# RaspiOMix.net
KiCad netlist of a schematic drawn in EAGLE
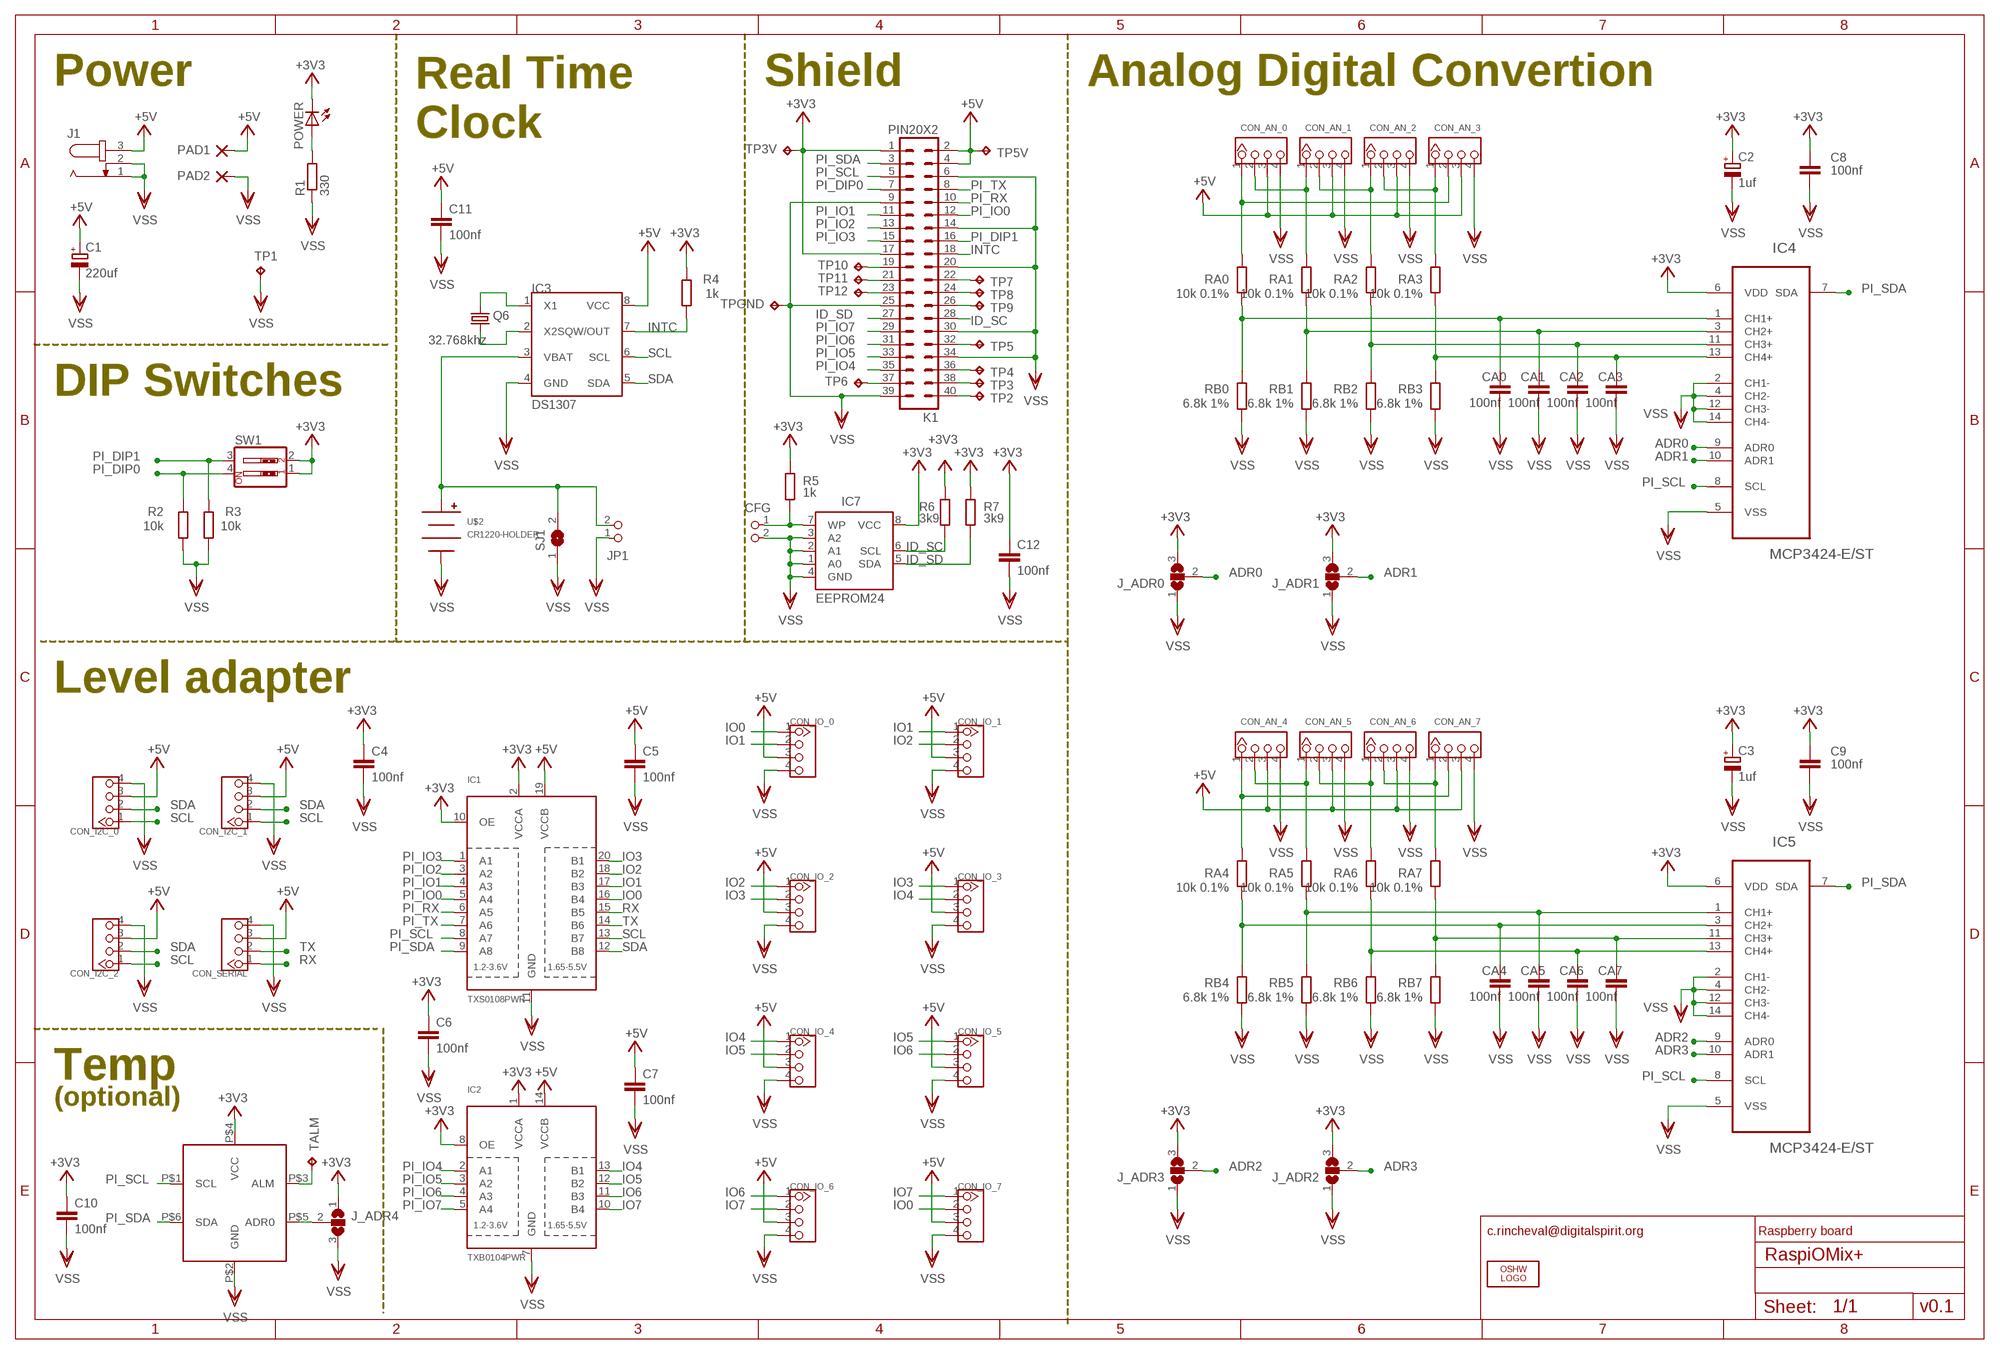
[diagram p0: schematic, sheet 1]

(export (version "E")
  (design (tool "Eeschema 10.0.6"))
  (components
    (comp (ref "C1")
      (value "220uf")
      (footprint "eagle-import:PANASONIC_D")
      (libsource (lib "eagle-import") (part "CPOL-EUD"))
    )
    (comp (ref "C2")
      (value "1uf")
      (footprint "eagle-import:B_3528-21R")
      (libsource (lib "eagle-import") (part "CPOL-EUB/3528-21R"))
    )
    (comp (ref "C3")
      (value "1uf")
      (footprint "eagle-import:B_3528-21R")
      (libsource (lib "eagle-import") (part "CPOL-EUB/3528-21R"))
    )
    (comp (ref "C4")
      (value "100nf")
      (footprint "eagle-import:C0805")
      (libsource (lib "eagle-import") (part "C-EUC0805"))
    )
    (comp (ref "C5")
      (value "100nf")
      (footprint "eagle-import:C0805")
      (libsource (lib "eagle-import") (part "C-EUC0805"))
    )
    (comp (ref "C6")
      (value "100nf")
      (footprint "eagle-import:C0805")
      (libsource (lib "eagle-import") (part "C-EUC0805"))
    )
    (comp (ref "C7")
      (value "100nf")
      (footprint "eagle-import:C0805")
      (libsource (lib "eagle-import") (part "C-EUC0805"))
    )
    (comp (ref "C8")
      (value "100nf")
      (footprint "eagle-import:C0805")
      (libsource (lib "eagle-import") (part "C-EUC0805"))
    )
    (comp (ref "C9")
      (value "100nf")
      (footprint "eagle-import:C0805")
      (libsource (lib "eagle-import") (part "C-EUC0805"))
    )
    (comp (ref "C10")
      (value "100nf")
      (footprint "eagle-import:C0805")
      (libsource (lib "eagle-import") (part "C-EUC0805"))
    )
    (comp (ref "C11")
      (value "100nf")
      (footprint "eagle-import:C0805")
      (libsource (lib "eagle-import") (part "C-EUC0805"))
    )
    (comp (ref "C12")
      (value "100nf")
      (footprint "eagle-import:C0805K")
      (libsource (lib "eagle-import") (part "resistor_C-EUC0805K"))
    )
    (comp (ref "CA0")
      (value "100nf")
      (footprint "eagle-import:C0805")
      (libsource (lib "eagle-import") (part "C-EUC0805"))
    )
    (comp (ref "CA1")
      (value "100nf")
      (footprint "eagle-import:C0805")
      (libsource (lib "eagle-import") (part "C-EUC0805"))
    )
    (comp (ref "CA2")
      (value "100nf")
      (footprint "eagle-import:C0805")
      (libsource (lib "eagle-import") (part "C-EUC0805"))
    )
    (comp (ref "CA3")
      (value "100nf")
      (footprint "eagle-import:C0805")
      (libsource (lib "eagle-import") (part "C-EUC0805"))
    )
    (comp (ref "CA4")
      (value "100nf")
      (footprint "eagle-import:C0805")
      (libsource (lib "eagle-import") (part "C-EUC0805"))
    )
    (comp (ref "CA5")
      (value "100nf")
      (footprint "eagle-import:C0805")
      (libsource (lib "eagle-import") (part "C-EUC0805"))
    )
    (comp (ref "CA6")
      (value "100nf")
      (footprint "eagle-import:C0805")
      (libsource (lib "eagle-import") (part "C-EUC0805"))
    )
    (comp (ref "CA7")
      (value "100nf")
      (footprint "eagle-import:C0805")
      (libsource (lib "eagle-import") (part "C-EUC0805"))
    )
    (comp (ref "CFG")
      (value "PIN2_100")
      (footprint "eagle-import:PIN_W_2")
      (libsource (lib "eagle-import") (part "PIN2_100"))
    )
    (comp (ref "CON_AN_0")
      (value "TWIG-4P-2.0-2.0")
      (footprint "eagle-import:4P-2.0")
      (libsource (lib "eagle-import") (part "TWIG-4P-2.0-2.0"))
    )
    (comp (ref "CON_AN_1")
      (value "TWIG-4P-2.0-2.0")
      (footprint "eagle-import:4P-2.0")
      (libsource (lib "eagle-import") (part "TWIG-4P-2.0-2.0"))
    )
    (comp (ref "CON_AN_2")
      (value "TWIG-4P-2.0-2.0")
      (footprint "eagle-import:4P-2.0")
      (libsource (lib "eagle-import") (part "TWIG-4P-2.0-2.0"))
    )
    (comp (ref "CON_AN_3")
      (value "TWIG-4P-2.0-2.0")
      (footprint "eagle-import:4P-2.0")
      (libsource (lib "eagle-import") (part "TWIG-4P-2.0-2.0"))
    )
    (comp (ref "CON_AN_4")
      (value "TWIG-4P-2.0-2.0")
      (footprint "eagle-import:4P-2.0")
      (libsource (lib "eagle-import") (part "TWIG-4P-2.0-2.0"))
    )
    (comp (ref "CON_AN_5")
      (value "TWIG-4P-2.0-2.0")
      (footprint "eagle-import:4P-2.0")
      (libsource (lib "eagle-import") (part "TWIG-4P-2.0-2.0"))
    )
    (comp (ref "CON_AN_6")
      (value "TWIG-4P-2.0-2.0")
      (footprint "eagle-import:4P-2.0")
      (libsource (lib "eagle-import") (part "TWIG-4P-2.0-2.0"))
    )
    (comp (ref "CON_AN_7")
      (value "TWIG-4P-2.0-2.0")
      (footprint "eagle-import:4P-2.0")
      (libsource (lib "eagle-import") (part "TWIG-4P-2.0-2.0"))
    )
    (comp (ref "CON_I2C_0")
      (value "TWIG-4P-2.0-2.0")
      (footprint "eagle-import:4P-2.0")
      (libsource (lib "eagle-import") (part "TWIG-4P-2.0-2.0"))
    )
    (comp (ref "CON_I2C_1")
      (value "TWIG-4P-2.0-2.0")
      (footprint "eagle-import:4P-2.0")
      (libsource (lib "eagle-import") (part "TWIG-4P-2.0-2.0"))
    )
    (comp (ref "CON_I2C_2")
      (value "TWIG-4P-2.0-2.0")
      (footprint "eagle-import:4P-2.0")
      (libsource (lib "eagle-import") (part "TWIG-4P-2.0-2.0"))
    )
    (comp (ref "CON_IO_0")
      (value "TWIG-4P-2.0-2.0")
      (footprint "eagle-import:4P-2.0")
      (libsource (lib "eagle-import") (part "TWIG-4P-2.0-2.0"))
    )
    (comp (ref "CON_IO_1")
      (value "TWIG-4P-2.0-2.0")
      (footprint "eagle-import:4P-2.0")
      (libsource (lib "eagle-import") (part "TWIG-4P-2.0-2.0"))
    )
    (comp (ref "CON_IO_2")
      (value "TWIG-4P-2.0-2.0")
      (footprint "eagle-import:4P-2.0")
      (libsource (lib "eagle-import") (part "TWIG-4P-2.0-2.0"))
    )
    (comp (ref "CON_IO_3")
      (value "TWIG-4P-2.0-2.0")
      (footprint "eagle-import:4P-2.0")
      (libsource (lib "eagle-import") (part "TWIG-4P-2.0-2.0"))
    )
    (comp (ref "CON_IO_4")
      (value "TWIG-4P-2.0-2.0")
      (footprint "eagle-import:4P-2.0")
      (libsource (lib "eagle-import") (part "TWIG-4P-2.0-2.0"))
    )
    (comp (ref "CON_IO_5")
      (value "TWIG-4P-2.0-2.0")
      (footprint "eagle-import:4P-2.0")
      (libsource (lib "eagle-import") (part "TWIG-4P-2.0-2.0"))
    )
    (comp (ref "CON_IO_6")
      (value "TWIG-4P-2.0-2.0")
      (footprint "eagle-import:4P-2.0")
      (libsource (lib "eagle-import") (part "TWIG-4P-2.0-2.0"))
    )
    (comp (ref "CON_IO_7")
      (value "TWIG-4P-2.0-2.0")
      (footprint "eagle-import:4P-2.0")
      (libsource (lib "eagle-import") (part "TWIG-4P-2.0-2.0"))
    )
    (comp (ref "CON_SERIAL")
      (value "TWIG-4P-2.0-2.0")
      (footprint "eagle-import:4P-2.0")
      (libsource (lib "eagle-import") (part "TWIG-4P-2.0-2.0"))
    )
    (comp (ref "IC1")
      (value "TXS0108PWR")
      (footprint "eagle-import:TSSOP20")
      (libsource (lib "eagle-import") (part "TXB0108PWR"))
    )
    (comp (ref "IC2")
      (value "TXB0104PWR")
      (footprint "eagle-import:TSSOP14")
      (libsource (lib "eagle-import") (part "TXB0104PWR"))
    )
    (comp (ref "IC3")
      (value "DS1307")
      (footprint "eagle-import:SOIC-8")
      (libsource (lib "eagle-import") (part "DS1307"))
    )
    (comp (ref "IC4")
      (value "MCP3424-E/ST")
      (footprint "eagle-import:SOP65P640X120-14N")
      (libsource (lib "eagle-import") (part "MCP3424-E/ST"))
    )
    (comp (ref "IC5")
      (value "MCP3424-E/ST")
      (footprint "eagle-import:SOP65P640X120-14N")
      (libsource (lib "eagle-import") (part "MCP3424-E/ST"))
    )
    (comp (ref "IC6")
      (value "TMP101")
      (footprint "eagle-import:SOT23-6")
      (libsource (lib "eagle-import") (part "TMP101"))
    )
    (comp (ref "IC7")
      (value "EEPROM24")
      (footprint "eagle-import:SOIC8")
      (libsource (lib "eagle-import") (part "EEPROM24"))
    )
    (comp (ref "J1")
      (value "JACK-PLUG0")
      (footprint "eagle-import:SPC4077")
      (libsource (lib "eagle-import") (part "JACK-PLUG0"))
    )
    (comp (ref "JP1")
      (value "PIN2_100")
      (footprint "eagle-import:PIN_W_2")
      (libsource (lib "eagle-import") (part "PIN2_100"))
    )
    (comp (ref "J_ADR0")
      (value "SJ2W")
      (footprint "eagle-import:SJ_2")
      (libsource (lib "eagle-import") (part "SJ2W"))
    )
    (comp (ref "J_ADR1")
      (value "SJ2W")
      (footprint "eagle-import:SJ_2")
      (libsource (lib "eagle-import") (part "SJ2W"))
    )
    (comp (ref "J_ADR2")
      (value "SJ2W")
      (footprint "eagle-import:SJ_2")
      (libsource (lib "eagle-import") (part "SJ2W"))
    )
    (comp (ref "J_ADR3")
      (value "SJ2W")
      (footprint "eagle-import:SJ_2")
      (libsource (lib "eagle-import") (part "SJ2W"))
    )
    (comp (ref "J_ADR4")
      (value "SJ2W")
      (footprint "eagle-import:SJ_2")
      (libsource (lib "eagle-import") (part "SJ2W"))
    )
    (comp (ref "K1")
      (value "PIN20X2")
      (footprint "eagle-import:PIN_20X2")
      (libsource (lib "eagle-import") (part "PIN20X2"))
    )
    (comp (ref "LOGO1")
      (value "OSHW_LOGO_FILLX0350-NT")
      (footprint "eagle-import:OSHW_FILLX350_NOTEXT")
      (libsource (lib "eagle-import") (part "OSHW_LOGO_FILLX0350-NT"))
    )
    (comp (ref "PAD1")
      (value "WIREPAD3,17/1,3")
      (footprint "eagle-import:3,17_1,3")
      (libsource (lib "eagle-import") (part "WIREPAD3,17/1,3"))
    )
    (comp (ref "PAD2")
      (value "WIREPAD3,17/1,3")
      (footprint "eagle-import:3,17_1,3")
      (libsource (lib "eagle-import") (part "WIREPAD3,17/1,3"))
    )
    (comp (ref "POWER")
      (value "LEDCHIPLED_0805")
      (footprint "eagle-import:CHIPLED_0805")
      (libsource (lib "eagle-import") (part "LEDCHIPLED_0805"))
    )
    (comp (ref "Q6")
      (value "32.768khz")
      (footprint "eagle-import:TC26H")
      (libsource (lib "eagle-import") (part "CRYSTALTC26H"))
    )
    (comp (ref "R1")
      (value "330")
      (footprint "eagle-import:M0805")
      (libsource (lib "eagle-import") (part "R-EU_M0805"))
    )
    (comp (ref "R2")
      (value "10k")
      (footprint "eagle-import:M0805")
      (libsource (lib "eagle-import") (part "R-EU_M0805"))
    )
    (comp (ref "R3")
      (value "10k")
      (footprint "eagle-import:M0805")
      (libsource (lib "eagle-import") (part "R-EU_M0805"))
    )
    (comp (ref "R4")
      (value "1k")
      (footprint "eagle-import:M0805")
      (libsource (lib "eagle-import") (part "R-EU_M0805"))
    )
    (comp (ref "R5")
      (value "1k")
      (footprint "eagle-import:M0805")
      (fields (field (name "TOLERANCE") "5%"))
      (libsource (lib "eagle-import") (part "resistor_R-EU_M0805"))
    )
    (comp (ref "R6")
      (value "3k9")
      (footprint "eagle-import:M0805")
      (fields (field (name "TOLERANCE") "5%"))
      (libsource (lib "eagle-import") (part "resistor_R-EU_M0805"))
    )
    (comp (ref "R7")
      (value "3k9")
      (footprint "eagle-import:M0805")
      (fields (field (name "TOLERANCE") "5%"))
      (libsource (lib "eagle-import") (part "resistor_R-EU_M0805"))
    )
    (comp (ref "RA0")
      (value "10k 0.1%")
      (footprint "eagle-import:M0805")
      (libsource (lib "eagle-import") (part "R-EU_M0805"))
    )
    (comp (ref "RA1")
      (value "10k 0.1%")
      (footprint "eagle-import:M0805")
      (libsource (lib "eagle-import") (part "R-EU_M0805"))
    )
    (comp (ref "RA2")
      (value "10k 0.1%")
      (footprint "eagle-import:M0805")
      (libsource (lib "eagle-import") (part "R-EU_M0805"))
    )
    (comp (ref "RA3")
      (value "10k 0.1%")
      (footprint "eagle-import:M0805")
      (libsource (lib "eagle-import") (part "R-EU_M0805"))
    )
    (comp (ref "RA4")
      (value "10k 0.1%")
      (footprint "eagle-import:M0805")
      (libsource (lib "eagle-import") (part "R-EU_M0805"))
    )
    (comp (ref "RA5")
      (value "10k 0.1%")
      (footprint "eagle-import:M0805")
      (libsource (lib "eagle-import") (part "R-EU_M0805"))
    )
    (comp (ref "RA6")
      (value "10k 0.1%")
      (footprint "eagle-import:M0805")
      (libsource (lib "eagle-import") (part "R-EU_M0805"))
    )
    (comp (ref "RA7")
      (value "10k 0.1%")
      (footprint "eagle-import:M0805")
      (libsource (lib "eagle-import") (part "R-EU_M0805"))
    )
    (comp (ref "RB0")
      (value "6.8k 1%")
      (footprint "eagle-import:M0805")
      (libsource (lib "eagle-import") (part "R-EU_M0805"))
    )
    (comp (ref "RB1")
      (value "6.8k 1%")
      (footprint "eagle-import:M0805")
      (libsource (lib "eagle-import") (part "R-EU_M0805"))
    )
    (comp (ref "RB2")
      (value "6.8k 1%")
      (footprint "eagle-import:M0805")
      (libsource (lib "eagle-import") (part "R-EU_M0805"))
    )
    (comp (ref "RB3")
      (value "6.8k 1%")
      (footprint "eagle-import:M0805")
      (libsource (lib "eagle-import") (part "R-EU_M0805"))
    )
    (comp (ref "RB4")
      (value "6.8k 1%")
      (footprint "eagle-import:M0805")
      (libsource (lib "eagle-import") (part "R-EU_M0805"))
    )
    (comp (ref "RB5")
      (value "6.8k 1%")
      (footprint "eagle-import:M0805")
      (libsource (lib "eagle-import") (part "R-EU_M0805"))
    )
    (comp (ref "RB6")
      (value "6.8k 1%")
      (footprint "eagle-import:M0805")
      (libsource (lib "eagle-import") (part "R-EU_M0805"))
    )
    (comp (ref "RB7")
      (value "6.8k 1%")
      (footprint "eagle-import:M0805")
      (libsource (lib "eagle-import") (part "R-EU_M0805"))
    )
    (comp (ref "SJ1") (value "SJ") (footprint "eagle-import:SJ") (libsource (lib "eagle-import") (part "SJ")))
    (comp (ref "SW1")
      (value "SW_DIP-2")
      (footprint "eagle-import:EDG-02")
      (libsource (lib "eagle-import") (part "SW_DIP-2"))
    )
    (comp (ref "TALM")
      (value "TPTP12R")
      (footprint "eagle-import:TP12R")
      (libsource (lib "eagle-import") (part "TPTP12R"))
    )
    (comp (ref "TP1")
      (value "TPPAD1-13")
      (footprint "eagle-import:P1-13")
      (libsource (lib "eagle-import") (part "TPPAD1-13"))
    )
    (comp (ref "TP2")
      (value "TPTP12R")
      (footprint "eagle-import:TP12R")
      (libsource (lib "eagle-import") (part "TPTP12R"))
    )
    (comp (ref "TP3")
      (value "TPTP12R")
      (footprint "eagle-import:TP12R")
      (libsource (lib "eagle-import") (part "TPTP12R"))
    )
    (comp (ref "TP3V")
      (value "TPTP12R")
      (footprint "eagle-import:TP12R")
      (libsource (lib "eagle-import") (part "TPTP12R"))
    )
    (comp (ref "TP4")
      (value "TPTP12R")
      (footprint "eagle-import:TP12R")
      (libsource (lib "eagle-import") (part "TPTP12R"))
    )
    (comp (ref "TP5")
      (value "TPTP12R")
      (footprint "eagle-import:TP12R")
      (libsource (lib "eagle-import") (part "TPTP12R"))
    )
    (comp (ref "TP5V")
      (value "TPTP12R")
      (footprint "eagle-import:TP12R")
      (libsource (lib "eagle-import") (part "TPTP12R"))
    )
    (comp (ref "TP6")
      (value "TPTP12R")
      (footprint "eagle-import:TP12R")
      (libsource (lib "eagle-import") (part "TPTP12R"))
    )
    (comp (ref "TP7")
      (value "TPTP12R")
      (footprint "eagle-import:TP12R")
      (libsource (lib "eagle-import") (part "TPTP12R"))
    )
    (comp (ref "TP8")
      (value "TPTP12R")
      (footprint "eagle-import:TP12R")
      (libsource (lib "eagle-import") (part "TPTP12R"))
    )
    (comp (ref "TP9")
      (value "TPTP12R")
      (footprint "eagle-import:TP12R")
      (libsource (lib "eagle-import") (part "TPTP12R"))
    )
    (comp (ref "TP10")
      (value "TPTP12R")
      (footprint "eagle-import:TP12R")
      (libsource (lib "eagle-import") (part "TPTP12R"))
    )
    (comp (ref "TP11")
      (value "TPTP12R")
      (footprint "eagle-import:TP12R")
      (libsource (lib "eagle-import") (part "TPTP12R"))
    )
    (comp (ref "TP12")
      (value "TPTP12R")
      (footprint "eagle-import:TP12R")
      (libsource (lib "eagle-import") (part "TPTP12R"))
    )
    (comp (ref "TPGND")
      (value "TPTP12R")
      (footprint "eagle-import:TP12R")
      (libsource (lib "eagle-import") (part "TPTP12R"))
    )
    (comp (ref "U$2")
      (value "CR1220-HOLDER")
      (footprint "eagle-import:HARWIN-CR1220")
      (libsource (lib "eagle-import") (part "CR1220-HOLDER"))
    )
  )
  (nets
    (net (code "1") (name "+3V3") (class "Default")
      (node (ref "C10") (pin "1") (pinfunction "1_1") (pintype "passive"))
      (node (ref "C12") (pin "1") (pinfunction "1_1") (pintype "passive"))
      (node (ref "C2") (pin "+") (pinfunction "+_+") (pintype "passive"))
      (node (ref "C3") (pin "+") (pinfunction "+_+") (pintype "passive"))
      (node (ref "C4") (pin "1") (pinfunction "1_1") (pintype "passive"))
      (node (ref "C6") (pin "1") (pinfunction "1_1") (pintype "passive"))
      (node (ref "C8") (pin "2") (pinfunction "2_2") (pintype "passive"))
      (node (ref "C9") (pin "2") (pinfunction "2_2") (pintype "passive"))
      (node (ref "IC1") (pin "10") (pinfunction "OE_10") (pintype "bidirectional"))
      (node (ref "IC1") (pin "2") (pinfunction "VCCA_2") (pintype "bidirectional"))
      (node (ref "IC2") (pin "1") (pinfunction "VCCA_1") (pintype "bidirectional"))
      (node (ref "IC2") (pin "8") (pinfunction "OE_8") (pintype "bidirectional"))
      (node (ref "IC4") (pin "6") (pinfunction "VDD_6") (pintype "power_in"))
      (node (ref "IC5") (pin "6") (pinfunction "VDD_6") (pintype "power_in"))
      (node (ref "IC6") (pin "P$4") (pinfunction "VCC_P$4") (pintype "power_in"))
      (node (ref "IC7") (pin "8") (pinfunction "VCC_8") (pintype "power_in"))
      (node (ref "J_ADR0") (pin "3") (pinfunction "3_3") (pintype "passive"))
      (node (ref "J_ADR1") (pin "3") (pinfunction "3_3") (pintype "passive"))
      (node (ref "J_ADR2") (pin "3") (pinfunction "3_3") (pintype "passive"))
      (node (ref "J_ADR3") (pin "3") (pinfunction "3_3") (pintype "passive"))
      (node (ref "J_ADR4") (pin "1") (pinfunction "1_1") (pintype "passive"))
      (node (ref "K1") (pin "1") (pinfunction "1_1") (pintype "passive"))
      (node (ref "K1") (pin "17") (pinfunction "17_17") (pintype "passive"))
      (node (ref "POWER") (pin "C") (pinfunction "C_C") (pintype "passive"))
      (node (ref "R4") (pin "2") (pinfunction "2_2") (pintype "passive"))
      (node (ref "R5") (pin "2") (pinfunction "2_2") (pintype "passive"))
      (node (ref "R6") (pin "2") (pinfunction "2_2") (pintype "passive"))
      (node (ref "R7") (pin "2") (pinfunction "2_2") (pintype "passive"))
      (node (ref "SW1") (pin "1") (pinfunction "1_1") (pintype "passive"))
      (node (ref "SW1") (pin "2") (pinfunction "2_2") (pintype "passive"))
      (node (ref "TP3V") (pin "TP") (pinfunction "TP_TP") (pintype "input"))
    )
    (net (code "2") (name "+5V") (class "Default")
      (node (ref "C1") (pin "+") (pinfunction "+_+") (pintype "passive"))
      (node (ref "C11") (pin "1") (pinfunction "1_1") (pintype "passive"))
      (node (ref "C5") (pin "1") (pinfunction "1_1") (pintype "passive"))
      (node (ref "C7") (pin "1") (pinfunction "1_1") (pintype "passive"))
      (node (ref "CON_AN_0") (pin "3") (pinfunction "3_3") (pintype "bidirectional"))
      (node (ref "CON_AN_1") (pin "3") (pinfunction "3_3") (pintype "bidirectional"))
      (node (ref "CON_AN_2") (pin "3") (pinfunction "3_3") (pintype "bidirectional"))
      (node (ref "CON_AN_3") (pin "3") (pinfunction "3_3") (pintype "bidirectional"))
      (node (ref "CON_AN_4") (pin "3") (pinfunction "3_3") (pintype "bidirectional"))
      (node (ref "CON_AN_5") (pin "3") (pinfunction "3_3") (pintype "bidirectional"))
      (node (ref "CON_AN_6") (pin "3") (pinfunction "3_3") (pintype "bidirectional"))
      (node (ref "CON_AN_7") (pin "3") (pinfunction "3_3") (pintype "bidirectional"))
      (node (ref "CON_I2C_0") (pin "3") (pinfunction "3_3") (pintype "bidirectional"))
      (node (ref "CON_I2C_1") (pin "3") (pinfunction "3_3") (pintype "bidirectional"))
      (node (ref "CON_I2C_2") (pin "3") (pinfunction "3_3") (pintype "bidirectional"))
      (node (ref "CON_IO_0") (pin "3") (pinfunction "3_3") (pintype "bidirectional"))
      (node (ref "CON_IO_1") (pin "3") (pinfunction "3_3") (pintype "bidirectional"))
      (node (ref "CON_IO_2") (pin "3") (pinfunction "3_3") (pintype "bidirectional"))
      (node (ref "CON_IO_3") (pin "3") (pinfunction "3_3") (pintype "bidirectional"))
      (node (ref "CON_IO_4") (pin "3") (pinfunction "3_3") (pintype "bidirectional"))
      (node (ref "CON_IO_5") (pin "3") (pinfunction "3_3") (pintype "bidirectional"))
      (node (ref "CON_IO_6") (pin "3") (pinfunction "3_3") (pintype "bidirectional"))
      (node (ref "CON_IO_7") (pin "3") (pinfunction "3_3") (pintype "bidirectional"))
      (node (ref "CON_SERIAL") (pin "3") (pinfunction "3_3") (pintype "bidirectional"))
      (node (ref "IC1") (pin "19") (pinfunction "VCCB_19") (pintype "bidirectional"))
      (node (ref "IC2") (pin "14") (pinfunction "VCCB_14") (pintype "bidirectional"))
      (node (ref "IC3") (pin "8") (pinfunction "VCC_8") (pintype "power_in"))
      (node (ref "J1") (pin "3") (pinfunction "3_3") (pintype "passive"))
      (node (ref "K1") (pin "2") (pinfunction "2_2") (pintype "passive"))
      (node (ref "K1") (pin "4") (pinfunction "4_4") (pintype "passive"))
      (node (ref "PAD1") (pin "1") (pinfunction "P_1") (pintype "passive"))
      (node (ref "TP5V") (pin "TP") (pinfunction "TP_TP") (pintype "input"))
    )
    (net (code "3") (name "/ADR0") (class "Default")
      (node (ref "IC4") (pin "9") (pinfunction "ADR0_9") (pintype "input"))
      (node (ref "J_ADR0") (pin "2") (pinfunction "2_2") (pintype "passive"))
    )
    (net (code "4") (name "/ADR1") (class "Default")
      (node (ref "IC4") (pin "10") (pinfunction "ADR1_10") (pintype "input"))
      (node (ref "J_ADR1") (pin "2") (pinfunction "2_2") (pintype "passive"))
    )
    (net (code "5") (name "/ADR2") (class "Default")
      (node (ref "IC5") (pin "9") (pinfunction "ADR0_9") (pintype "input"))
      (node (ref "J_ADR3") (pin "2") (pinfunction "2_2") (pintype "passive"))
    )
    (net (code "6") (name "/ADR3") (class "Default")
      (node (ref "IC5") (pin "10") (pinfunction "ADR1_10") (pintype "input"))
      (node (ref "J_ADR2") (pin "2") (pinfunction "2_2") (pintype "passive"))
    )
    (net (code "7") (name "/ID_SC") (class "Default")
      (node (ref "IC7") (pin "6") (pinfunction "SCL_6") (pintype "input"))
      (node (ref "K1") (pin "28") (pinfunction "28_28") (pintype "passive"))
      (node (ref "R6") (pin "1") (pinfunction "1_1") (pintype "passive"))
    )
    (net (code "8") (name "/ID_SD") (class "Default")
      (node (ref "IC7") (pin "5") (pinfunction "SDA_5") (pintype "bidirectional"))
      (node (ref "K1") (pin "27") (pinfunction "27_27") (pintype "passive"))
      (node (ref "R7") (pin "1") (pinfunction "1_1") (pintype "passive"))
    )
    (net (code "9") (name "/INTC") (class "Default")
      (node (ref "IC3") (pin "7") (pinfunction "SQW/OUT_7") (pintype "output"))
      (node (ref "K1") (pin "18") (pinfunction "18_18") (pintype "passive"))
      (node (ref "R4") (pin "1") (pinfunction "1_1") (pintype "passive"))
    )
    (net (code "10") (name "/IO0") (class "Default")
      (node (ref "CON_IO_0") (pin "1") (pinfunction "1_1") (pintype "bidirectional"))
      (node (ref "CON_IO_7") (pin "2") (pinfunction "2_2") (pintype "bidirectional"))
      (node (ref "IC1") (pin "16") (pinfunction "B4_16") (pintype "bidirectional"))
    )
    (net (code "11") (name "/IO1") (class "Default")
      (node (ref "CON_IO_0") (pin "2") (pinfunction "2_2") (pintype "bidirectional"))
      (node (ref "CON_IO_1") (pin "1") (pinfunction "1_1") (pintype "bidirectional"))
      (node (ref "IC1") (pin "17") (pinfunction "B3_17") (pintype "bidirectional"))
    )
    (net (code "12") (name "/IO2") (class "Default")
      (node (ref "CON_IO_1") (pin "2") (pinfunction "2_2") (pintype "bidirectional"))
      (node (ref "CON_IO_2") (pin "1") (pinfunction "1_1") (pintype "bidirectional"))
      (node (ref "IC1") (pin "18") (pinfunction "B2_18") (pintype "bidirectional"))
    )
    (net (code "13") (name "/IO3") (class "Default")
      (node (ref "CON_IO_2") (pin "2") (pinfunction "2_2") (pintype "bidirectional"))
      (node (ref "CON_IO_3") (pin "1") (pinfunction "1_1") (pintype "bidirectional"))
      (node (ref "IC1") (pin "20") (pinfunction "B1_20") (pintype "bidirectional"))
    )
    (net (code "14") (name "/IO4") (class "Default")
      (node (ref "CON_IO_3") (pin "2") (pinfunction "2_2") (pintype "bidirectional"))
      (node (ref "CON_IO_4") (pin "1") (pinfunction "1_1") (pintype "bidirectional"))
      (node (ref "IC2") (pin "13") (pinfunction "B1_13") (pintype "bidirectional"))
    )
    (net (code "15") (name "/IO5") (class "Default")
      (node (ref "CON_IO_4") (pin "2") (pinfunction "2_2") (pintype "bidirectional"))
      (node (ref "CON_IO_5") (pin "1") (pinfunction "1_1") (pintype "bidirectional"))
      (node (ref "IC2") (pin "12") (pinfunction "B2_12") (pintype "bidirectional"))
    )
    (net (code "16") (name "/IO6") (class "Default")
      (node (ref "CON_IO_5") (pin "2") (pinfunction "2_2") (pintype "bidirectional"))
      (node (ref "CON_IO_6") (pin "1") (pinfunction "1_1") (pintype "bidirectional"))
      (node (ref "IC2") (pin "11") (pinfunction "B3_11") (pintype "bidirectional"))
    )
    (net (code "17") (name "/IO7") (class "Default")
      (node (ref "CON_IO_6") (pin "2") (pinfunction "2_2") (pintype "bidirectional"))
      (node (ref "CON_IO_7") (pin "1") (pinfunction "1_1") (pintype "bidirectional"))
      (node (ref "IC2") (pin "10") (pinfunction "B4_10") (pintype "bidirectional"))
    )
    (net (code "18") (name "/PI_DIP0") (class "Default")
      (node (ref "K1") (pin "7") (pinfunction "7_7") (pintype "passive"))
      (node (ref "R2") (pin "2") (pinfunction "2_2") (pintype "passive"))
      (node (ref "SW1") (pin "4") (pinfunction "4_4") (pintype "passive"))
    )
    (net (code "19") (name "/PI_DIP1") (class "Default")
      (node (ref "K1") (pin "16") (pinfunction "16_16") (pintype "passive"))
      (node (ref "R3") (pin "2") (pinfunction "2_2") (pintype "passive"))
      (node (ref "SW1") (pin "3") (pinfunction "3_3") (pintype "passive"))
    )
    (net (code "20") (name "/PI_IO0") (class "Default")
      (node (ref "IC1") (pin "5") (pinfunction "A4_5") (pintype "bidirectional"))
      (node (ref "K1") (pin "12") (pinfunction "12_12") (pintype "passive"))
    )
    (net (code "21") (name "/PI_IO1") (class "Default")
      (node (ref "IC1") (pin "4") (pinfunction "A3_4") (pintype "bidirectional"))
      (node (ref "K1") (pin "11") (pinfunction "11_11") (pintype "passive"))
    )
    (net (code "22") (name "/PI_IO2") (class "Default")
      (node (ref "IC1") (pin "3") (pinfunction "A2_3") (pintype "bidirectional"))
      (node (ref "K1") (pin "13") (pinfunction "13_13") (pintype "passive"))
    )
    (net (code "23") (name "/PI_IO3") (class "Default")
      (node (ref "IC1") (pin "1") (pinfunction "A1_1") (pintype "bidirectional"))
      (node (ref "K1") (pin "15") (pinfunction "15_15") (pintype "passive"))
    )
    (net (code "24") (name "/PI_IO4") (class "Default")
      (node (ref "IC2") (pin "2") (pinfunction "A1_2") (pintype "bidirectional"))
      (node (ref "K1") (pin "35") (pinfunction "35_35") (pintype "passive"))
    )
    (net (code "25") (name "/PI_IO5") (class "Default")
      (node (ref "IC2") (pin "3") (pinfunction "A2_3") (pintype "bidirectional"))
      (node (ref "K1") (pin "33") (pinfunction "33_33") (pintype "passive"))
    )
    (net (code "26") (name "/PI_IO6") (class "Default")
      (node (ref "IC2") (pin "4") (pinfunction "A3_4") (pintype "bidirectional"))
      (node (ref "K1") (pin "31") (pinfunction "31_31") (pintype "passive"))
    )
    (net (code "27") (name "/PI_IO7") (class "Default")
      (node (ref "IC2") (pin "5") (pinfunction "A4_5") (pintype "bidirectional"))
      (node (ref "K1") (pin "29") (pinfunction "29_29") (pintype "passive"))
    )
    (net (code "28") (name "/PI_RX") (class "Default")
      (node (ref "IC1") (pin "6") (pinfunction "A5_6") (pintype "bidirectional"))
      (node (ref "K1") (pin "10") (pinfunction "10_10") (pintype "passive"))
    )
    (net (code "29") (name "/PI_SCL") (class "Default")
      (node (ref "IC1") (pin "8") (pinfunction "A7_8") (pintype "bidirectional"))
      (node (ref "IC4") (pin "8") (pinfunction "SCL_8") (pintype "input"))
      (node (ref "IC5") (pin "8") (pinfunction "SCL_8") (pintype "input"))
      (node (ref "IC6") (pin "P$1") (pinfunction "SCL_P$1") (pintype "bidirectional"))
      (node (ref "K1") (pin "5") (pinfunction "5_5") (pintype "passive"))
    )
    (net (code "30") (name "/PI_SDA") (class "Default")
      (node (ref "IC1") (pin "9") (pinfunction "A8_9") (pintype "bidirectional"))
      (node (ref "IC4") (pin "7") (pinfunction "SDA_7") (pintype "bidirectional"))
      (node (ref "IC5") (pin "7") (pinfunction "SDA_7") (pintype "bidirectional"))
      (node (ref "IC6") (pin "P$6") (pinfunction "SDA_P$6") (pintype "bidirectional"))
      (node (ref "K1") (pin "3") (pinfunction "3_3") (pintype "passive"))
    )
    (net (code "31") (name "/PI_TX") (class "Default")
      (node (ref "IC1") (pin "7") (pinfunction "A6_7") (pintype "bidirectional"))
      (node (ref "K1") (pin "8") (pinfunction "8_8") (pintype "passive"))
    )
    (net (code "32") (name "/RX") (class "Default")
      (node (ref "CON_SERIAL") (pin "1") (pinfunction "1_1") (pintype "bidirectional"))
      (node (ref "IC1") (pin "15") (pinfunction "B5_15") (pintype "bidirectional"))
    )
    (net (code "33") (name "/SCL") (class "Default")
      (node (ref "CON_I2C_0") (pin "1") (pinfunction "1_1") (pintype "bidirectional"))
      (node (ref "CON_I2C_1") (pin "1") (pinfunction "1_1") (pintype "bidirectional"))
      (node (ref "CON_I2C_2") (pin "1") (pinfunction "1_1") (pintype "bidirectional"))
      (node (ref "IC1") (pin "13") (pinfunction "B7_13") (pintype "bidirectional"))
      (node (ref "IC3") (pin "6") (pinfunction "SCL_6") (pintype "input"))
    )
    (net (code "34") (name "/SDA") (class "Default")
      (node (ref "CON_I2C_0") (pin "2") (pinfunction "2_2") (pintype "bidirectional"))
      (node (ref "CON_I2C_1") (pin "2") (pinfunction "2_2") (pintype "bidirectional"))
      (node (ref "CON_I2C_2") (pin "2") (pinfunction "2_2") (pintype "bidirectional"))
      (node (ref "IC1") (pin "12") (pinfunction "B8_12") (pintype "bidirectional"))
      (node (ref "IC3") (pin "5") (pinfunction "SDA_5") (pintype "bidirectional"))
    )
    (net (code "35") (name "/TX") (class "Default")
      (node (ref "CON_SERIAL") (pin "2") (pinfunction "2_2") (pintype "bidirectional"))
      (node (ref "IC1") (pin "14") (pinfunction "B6_14") (pintype "bidirectional"))
    )
    (net (code "36") (name "Net-(CON_AN_0-Pad1)") (class "Default")
      (node (ref "CON_AN_0") (pin "1") (pinfunction "1_1") (pintype "bidirectional"))
      (node (ref "CON_AN_3") (pin "2") (pinfunction "2_2") (pintype "bidirectional"))
      (node (ref "RA0") (pin "2") (pinfunction "2_2") (pintype "passive"))
    )
    (net (code "37") (name "Net-(CON_AN_0-Pad2)") (class "Default")
      (node (ref "CON_AN_0") (pin "2") (pinfunction "2_2") (pintype "bidirectional"))
      (node (ref "CON_AN_1") (pin "1") (pinfunction "1_1") (pintype "bidirectional"))
      (node (ref "RA1") (pin "2") (pinfunction "2_2") (pintype "passive"))
    )
    (net (code "38") (name "Net-(CON_AN_1-Pad2)") (class "Default")
      (node (ref "CON_AN_1") (pin "2") (pinfunction "2_2") (pintype "bidirectional"))
      (node (ref "CON_AN_2") (pin "1") (pinfunction "1_1") (pintype "bidirectional"))
      (node (ref "RA2") (pin "2") (pinfunction "2_2") (pintype "passive"))
    )
    (net (code "39") (name "Net-(CON_AN_2-Pad2)") (class "Default")
      (node (ref "CON_AN_2") (pin "2") (pinfunction "2_2") (pintype "bidirectional"))
      (node (ref "CON_AN_3") (pin "1") (pinfunction "1_1") (pintype "bidirectional"))
      (node (ref "RA3") (pin "2") (pinfunction "2_2") (pintype "passive"))
    )
    (net (code "40") (name "Net-(CON_AN_4-Pad1)") (class "Default")
      (node (ref "CON_AN_4") (pin "1") (pinfunction "1_1") (pintype "bidirectional"))
      (node (ref "CON_AN_7") (pin "2") (pinfunction "2_2") (pintype "bidirectional"))
      (node (ref "RA4") (pin "2") (pinfunction "2_2") (pintype "passive"))
    )
    (net (code "41") (name "Net-(CON_AN_4-Pad2)") (class "Default")
      (node (ref "CON_AN_4") (pin "2") (pinfunction "2_2") (pintype "bidirectional"))
      (node (ref "CON_AN_5") (pin "1") (pinfunction "1_1") (pintype "bidirectional"))
      (node (ref "RA5") (pin "2") (pinfunction "2_2") (pintype "passive"))
    )
    (net (code "42") (name "Net-(CON_AN_5-Pad2)") (class "Default")
      (node (ref "CON_AN_5") (pin "2") (pinfunction "2_2") (pintype "bidirectional"))
      (node (ref "CON_AN_6") (pin "1") (pinfunction "1_1") (pintype "bidirectional"))
      (node (ref "RA6") (pin "2") (pinfunction "2_2") (pintype "passive"))
    )
    (net (code "43") (name "Net-(CON_AN_6-Pad2)") (class "Default")
      (node (ref "CON_AN_6") (pin "2") (pinfunction "2_2") (pintype "bidirectional"))
      (node (ref "CON_AN_7") (pin "1") (pinfunction "1_1") (pintype "bidirectional"))
      (node (ref "RA7") (pin "2") (pinfunction "2_2") (pintype "passive"))
    )
    (net (code "44") (name "Net-(IC3-VBAT)") (class "Default")
      (node (ref "IC3") (pin "3") (pinfunction "VBAT_3") (pintype "power_in"))
      (node (ref "JP1") (pin "2") (pinfunction "2_2") (pintype "passive"))
      (node (ref "SJ1") (pin "2") (pinfunction "2_2") (pintype "passive"))
      (node (ref "U$2") (pin "POS") (pinfunction "POS_POS") (pintype "bidirectional"))
    )
    (net (code "45") (name "Net-(IC3-X1)") (class "Default")
      (node (ref "IC3") (pin "1") (pinfunction "X1_1") (pintype "input"))
      (node (ref "Q6") (pin "1") (pinfunction "1_1") (pintype "passive"))
    )
    (net (code "46") (name "Net-(IC3-X2)") (class "Default")
      (node (ref "IC3") (pin "2") (pinfunction "X2_2") (pintype "output"))
      (node (ref "Q6") (pin "2") (pinfunction "2_2") (pintype "passive"))
    )
    (net (code "47") (name "Net-(IC4-CH1+)") (class "Default")
      (node (ref "CA0") (pin "1") (pinfunction "1_1") (pintype "passive"))
      (node (ref "IC4") (pin "1") (pinfunction "CH1+_1") (pintype "input"))
      (node (ref "RA0") (pin "1") (pinfunction "1_1") (pintype "passive"))
      (node (ref "RB0") (pin "2") (pinfunction "2_2") (pintype "passive"))
    )
    (net (code "48") (name "Net-(IC4-CH2+)") (class "Default")
      (node (ref "CA1") (pin "1") (pinfunction "1_1") (pintype "passive"))
      (node (ref "IC4") (pin "3") (pinfunction "CH2+_3") (pintype "input"))
      (node (ref "RA1") (pin "1") (pinfunction "1_1") (pintype "passive"))
      (node (ref "RB1") (pin "2") (pinfunction "2_2") (pintype "passive"))
    )
    (net (code "49") (name "Net-(IC4-CH3+)") (class "Default")
      (node (ref "CA2") (pin "1") (pinfunction "1_1") (pintype "passive"))
      (node (ref "IC4") (pin "11") (pinfunction "CH3+_11") (pintype "input"))
      (node (ref "RA2") (pin "1") (pinfunction "1_1") (pintype "passive"))
      (node (ref "RB2") (pin "2") (pinfunction "2_2") (pintype "passive"))
    )
    (net (code "50") (name "Net-(IC4-CH4+)") (class "Default")
      (node (ref "CA3") (pin "1") (pinfunction "1_1") (pintype "passive"))
      (node (ref "IC4") (pin "13") (pinfunction "CH4+_13") (pintype "input"))
      (node (ref "RA3") (pin "1") (pinfunction "1_1") (pintype "passive"))
      (node (ref "RB3") (pin "2") (pinfunction "2_2") (pintype "passive"))
    )
    (net (code "51") (name "Net-(IC5-CH1+)") (class "Default")
      (node (ref "CA5") (pin "1") (pinfunction "1_1") (pintype "passive"))
      (node (ref "IC5") (pin "1") (pinfunction "CH1+_1") (pintype "input"))
      (node (ref "RA5") (pin "1") (pinfunction "1_1") (pintype "passive"))
      (node (ref "RB5") (pin "2") (pinfunction "2_2") (pintype "passive"))
    )
    (net (code "52") (name "Net-(IC5-CH2+)") (class "Default")
      (node (ref "CA4") (pin "1") (pinfunction "1_1") (pintype "passive"))
      (node (ref "IC5") (pin "3") (pinfunction "CH2+_3") (pintype "input"))
      (node (ref "RA4") (pin "1") (pinfunction "1_1") (pintype "passive"))
      (node (ref "RB4") (pin "2") (pinfunction "2_2") (pintype "passive"))
    )
    (net (code "53") (name "Net-(IC5-CH3+)") (class "Default")
      (node (ref "CA7") (pin "1") (pinfunction "1_1") (pintype "passive"))
      (node (ref "IC5") (pin "11") (pinfunction "CH3+_11") (pintype "input"))
      (node (ref "RA7") (pin "1") (pinfunction "1_1") (pintype "passive"))
      (node (ref "RB7") (pin "2") (pinfunction "2_2") (pintype "passive"))
    )
    (net (code "54") (name "Net-(IC5-CH4+)") (class "Default")
      (node (ref "CA6") (pin "1") (pinfunction "1_1") (pintype "passive"))
      (node (ref "IC5") (pin "13") (pinfunction "CH4+_13") (pintype "input"))
      (node (ref "RA6") (pin "1") (pinfunction "1_1") (pintype "passive"))
      (node (ref "RB6") (pin "2") (pinfunction "2_2") (pintype "passive"))
    )
    (net (code "55") (name "Net-(IC6-ADR0)") (class "Default")
      (node (ref "IC6") (pin "P$5") (pinfunction "ADR0_P$5") (pintype "bidirectional"))
      (node (ref "J_ADR4") (pin "2") (pinfunction "2_2") (pintype "passive"))
    )
    (net (code "56") (name "Net-(IC6-ALM)") (class "Default")
      (node (ref "IC6") (pin "P$3") (pinfunction "ALM_P$3") (pintype "bidirectional"))
      (node (ref "TALM") (pin "TP") (pinfunction "TP_TP") (pintype "input"))
    )
    (net (code "57") (name "Net-(IC7-WP)") (class "Default")
      (node (ref "CFG") (pin "1") (pinfunction "1_1") (pintype "passive"))
      (node (ref "IC7") (pin "7") (pinfunction "WP_7") (pintype "input"))
      (node (ref "R5") (pin "1") (pinfunction "1_1") (pintype "passive"))
    )
    (net (code "58") (name "Net-(K1-Pad19)") (class "Default")
      (node (ref "K1") (pin "19") (pinfunction "19_19") (pintype "passive"))
      (node (ref "TP10") (pin "TP") (pinfunction "TP_TP") (pintype "input"))
    )
    (net (code "59") (name "Net-(K1-Pad21)") (class "Default")
      (node (ref "K1") (pin "21") (pinfunction "21_21") (pintype "passive"))
      (node (ref "TP11") (pin "TP") (pinfunction "TP_TP") (pintype "input"))
    )
    (net (code "60") (name "Net-(K1-Pad22)") (class "Default")
      (node (ref "K1") (pin "22") (pinfunction "22_22") (pintype "passive"))
      (node (ref "TP7") (pin "TP") (pinfunction "TP_TP") (pintype "input"))
    )
    (net (code "61") (name "Net-(K1-Pad23)") (class "Default")
      (node (ref "K1") (pin "23") (pinfunction "23_23") (pintype "passive"))
      (node (ref "TP12") (pin "TP") (pinfunction "TP_TP") (pintype "input"))
    )
    (net (code "62") (name "Net-(K1-Pad24)") (class "Default")
      (node (ref "K1") (pin "24") (pinfunction "24_24") (pintype "passive"))
      (node (ref "TP8") (pin "TP") (pinfunction "TP_TP") (pintype "input"))
    )
    (net (code "63") (name "Net-(K1-Pad26)") (class "Default")
      (node (ref "K1") (pin "26") (pinfunction "26_26") (pintype "passive"))
      (node (ref "TP9") (pin "TP") (pinfunction "TP_TP") (pintype "input"))
    )
    (net (code "64") (name "Net-(K1-Pad32)") (class "Default")
      (node (ref "K1") (pin "32") (pinfunction "32_32") (pintype "passive"))
      (node (ref "TP5") (pin "TP") (pinfunction "TP_TP") (pintype "input"))
    )
    (net (code "65") (name "Net-(K1-Pad36)") (class "Default")
      (node (ref "K1") (pin "36") (pinfunction "36_36") (pintype "passive"))
      (node (ref "TP4") (pin "TP") (pinfunction "TP_TP") (pintype "input"))
    )
    (net (code "66") (name "Net-(K1-Pad37)") (class "Default")
      (node (ref "K1") (pin "37") (pinfunction "37_37") (pintype "passive"))
      (node (ref "TP6") (pin "TP") (pinfunction "TP_TP") (pintype "input"))
    )
    (net (code "67") (name "Net-(K1-Pad38)") (class "Default")
      (node (ref "K1") (pin "38") (pinfunction "38_38") (pintype "passive"))
      (node (ref "TP3") (pin "TP") (pinfunction "TP_TP") (pintype "input"))
    )
    (net (code "68") (name "Net-(K1-Pad40)") (class "Default")
      (node (ref "K1") (pin "40") (pinfunction "40_40") (pintype "passive"))
      (node (ref "TP2") (pin "TP") (pinfunction "TP_TP") (pintype "input"))
    )
    (net (code "69") (name "Net-(POWER-PadA)") (class "Default")
      (node (ref "POWER") (pin "A") (pinfunction "A_A") (pintype "passive"))
      (node (ref "R1") (pin "2") (pinfunction "2_2") (pintype "passive"))
    )
    (net (code "70") (name "VSS") (class "Default")
      (node (ref "C1") (pin "-") (pinfunction "-_-") (pintype "passive"))
      (node (ref "C10") (pin "2") (pinfunction "2_2") (pintype "passive"))
      (node (ref "C11") (pin "2") (pinfunction "2_2") (pintype "passive"))
      (node (ref "C12") (pin "2") (pinfunction "2_2") (pintype "passive"))
      (node (ref "C2") (pin "-") (pinfunction "-_-") (pintype "passive"))
      (node (ref "C3") (pin "-") (pinfunction "-_-") (pintype "passive"))
      (node (ref "C4") (pin "2") (pinfunction "2_2") (pintype "passive"))
      (node (ref "C5") (pin "2") (pinfunction "2_2") (pintype "passive"))
      (node (ref "C6") (pin "2") (pinfunction "2_2") (pintype "passive"))
      (node (ref "C7") (pin "2") (pinfunction "2_2") (pintype "passive"))
      (node (ref "C8") (pin "1") (pinfunction "1_1") (pintype "passive"))
      (node (ref "C9") (pin "1") (pinfunction "1_1") (pintype "passive"))
      (node (ref "CA0") (pin "2") (pinfunction "2_2") (pintype "passive"))
      (node (ref "CA1") (pin "2") (pinfunction "2_2") (pintype "passive"))
      (node (ref "CA2") (pin "2") (pinfunction "2_2") (pintype "passive"))
      (node (ref "CA3") (pin "2") (pinfunction "2_2") (pintype "passive"))
      (node (ref "CA4") (pin "2") (pinfunction "2_2") (pintype "passive"))
      (node (ref "CA5") (pin "2") (pinfunction "2_2") (pintype "passive"))
      (node (ref "CA6") (pin "2") (pinfunction "2_2") (pintype "passive"))
      (node (ref "CA7") (pin "2") (pinfunction "2_2") (pintype "passive"))
      (node (ref "CFG") (pin "2") (pinfunction "2_2") (pintype "passive"))
      (node (ref "CON_AN_0") (pin "4") (pinfunction "4_4") (pintype "bidirectional"))
      (node (ref "CON_AN_1") (pin "4") (pinfunction "4_4") (pintype "bidirectional"))
      (node (ref "CON_AN_2") (pin "4") (pinfunction "4_4") (pintype "bidirectional"))
      (node (ref "CON_AN_3") (pin "4") (pinfunction "4_4") (pintype "bidirectional"))
      (node (ref "CON_AN_4") (pin "4") (pinfunction "4_4") (pintype "bidirectional"))
      (node (ref "CON_AN_5") (pin "4") (pinfunction "4_4") (pintype "bidirectional"))
      (node (ref "CON_AN_6") (pin "4") (pinfunction "4_4") (pintype "bidirectional"))
      (node (ref "CON_AN_7") (pin "4") (pinfunction "4_4") (pintype "bidirectional"))
      (node (ref "CON_I2C_0") (pin "4") (pinfunction "4_4") (pintype "bidirectional"))
      (node (ref "CON_I2C_1") (pin "4") (pinfunction "4_4") (pintype "bidirectional"))
      (node (ref "CON_I2C_2") (pin "4") (pinfunction "4_4") (pintype "bidirectional"))
      (node (ref "CON_IO_0") (pin "4") (pinfunction "4_4") (pintype "bidirectional"))
      (node (ref "CON_IO_1") (pin "4") (pinfunction "4_4") (pintype "bidirectional"))
      (node (ref "CON_IO_2") (pin "4") (pinfunction "4_4") (pintype "bidirectional"))
      (node (ref "CON_IO_3") (pin "4") (pinfunction "4_4") (pintype "bidirectional"))
      (node (ref "CON_IO_4") (pin "4") (pinfunction "4_4") (pintype "bidirectional"))
      (node (ref "CON_IO_5") (pin "4") (pinfunction "4_4") (pintype "bidirectional"))
      (node (ref "CON_IO_6") (pin "4") (pinfunction "4_4") (pintype "bidirectional"))
      (node (ref "CON_IO_7") (pin "4") (pinfunction "4_4") (pintype "bidirectional"))
      (node (ref "CON_SERIAL") (pin "4") (pinfunction "4_4") (pintype "bidirectional"))
      (node (ref "IC1") (pin "11") (pinfunction "GND_11") (pintype "bidirectional"))
      (node (ref "IC2") (pin "7") (pinfunction "GND_7") (pintype "bidirectional"))
      (node (ref "IC3") (pin "4") (pinfunction "GND_4") (pintype "power_in"))
      (node (ref "IC4") (pin "12") (pinfunction "CH3-_12") (pintype "input"))
      (node (ref "IC4") (pin "14") (pinfunction "CH4-_14") (pintype "input"))
      (node (ref "IC4") (pin "2") (pinfunction "CH1-_2") (pintype "input"))
      (node (ref "IC4") (pin "4") (pinfunction "CH2-_4") (pintype "input"))
      (node (ref "IC4") (pin "5") (pinfunction "VSS_5") (pintype "power_in"))
      (node (ref "IC5") (pin "12") (pinfunction "CH3-_12") (pintype "input"))
      (node (ref "IC5") (pin "14") (pinfunction "CH4-_14") (pintype "input"))
      (node (ref "IC5") (pin "2") (pinfunction "CH1-_2") (pintype "input"))
      (node (ref "IC5") (pin "4") (pinfunction "CH2-_4") (pintype "input"))
      (node (ref "IC5") (pin "5") (pinfunction "VSS_5") (pintype "power_in"))
      (node (ref "IC6") (pin "P$2") (pinfunction "GND_P$2") (pintype "power_in"))
      (node (ref "IC7") (pin "1") (pinfunction "A0_1") (pintype "input"))
      (node (ref "IC7") (pin "2") (pinfunction "A1_2") (pintype "input"))
      (node (ref "IC7") (pin "3") (pinfunction "A2_3") (pintype "input"))
      (node (ref "IC7") (pin "4") (pinfunction "GND_4") (pintype "power_in"))
      (node (ref "J1") (pin "1") (pinfunction "1_1") (pintype "passive"))
      (node (ref "J1") (pin "2") (pinfunction "2_2") (pintype "passive"))
      (node (ref "JP1") (pin "1") (pinfunction "1_1") (pintype "passive"))
      (node (ref "J_ADR0") (pin "1") (pinfunction "1_1") (pintype "passive"))
      (node (ref "J_ADR1") (pin "1") (pinfunction "1_1") (pintype "passive"))
      (node (ref "J_ADR2") (pin "1") (pinfunction "1_1") (pintype "passive"))
      (node (ref "J_ADR3") (pin "1") (pinfunction "1_1") (pintype "passive"))
      (node (ref "J_ADR4") (pin "3") (pinfunction "3_3") (pintype "passive"))
      (node (ref "K1") (pin "14") (pinfunction "14_14") (pintype "passive"))
      (node (ref "K1") (pin "20") (pinfunction "20_20") (pintype "passive"))
      (node (ref "K1") (pin "25") (pinfunction "25_25") (pintype "passive"))
      (node (ref "K1") (pin "30") (pinfunction "30_30") (pintype "passive"))
      (node (ref "K1") (pin "34") (pinfunction "34_34") (pintype "passive"))
      (node (ref "K1") (pin "39") (pinfunction "39_39") (pintype "passive"))
      (node (ref "K1") (pin "6") (pinfunction "6_6") (pintype "passive"))
      (node (ref "K1") (pin "9") (pinfunction "9_9") (pintype "passive"))
      (node (ref "PAD2") (pin "1") (pinfunction "P_1") (pintype "passive"))
      (node (ref "R1") (pin "1") (pinfunction "1_1") (pintype "passive"))
      (node (ref "R2") (pin "1") (pinfunction "1_1") (pintype "passive"))
      (node (ref "R3") (pin "1") (pinfunction "1_1") (pintype "passive"))
      (node (ref "RB0") (pin "1") (pinfunction "1_1") (pintype "passive"))
      (node (ref "RB1") (pin "1") (pinfunction "1_1") (pintype "passive"))
      (node (ref "RB2") (pin "1") (pinfunction "1_1") (pintype "passive"))
      (node (ref "RB3") (pin "1") (pinfunction "1_1") (pintype "passive"))
      (node (ref "RB4") (pin "1") (pinfunction "1_1") (pintype "passive"))
      (node (ref "RB5") (pin "1") (pinfunction "1_1") (pintype "passive"))
      (node (ref "RB6") (pin "1") (pinfunction "1_1") (pintype "passive"))
      (node (ref "RB7") (pin "1") (pinfunction "1_1") (pintype "passive"))
      (node (ref "SJ1") (pin "1") (pinfunction "1_1") (pintype "passive"))
      (node (ref "TP1") (pin "TP") (pinfunction "TP_TP") (pintype "input"))
      (node (ref "TPGND") (pin "TP") (pinfunction "TP_TP") (pintype "input"))
      (node (ref "U$2") (pin "NEG") (pinfunction "NEG_NEG") (pintype "bidirectional"))
    )
  )
)
